# Sheet2.net
KiCad netlist of a schematic drawn in Altium Designer
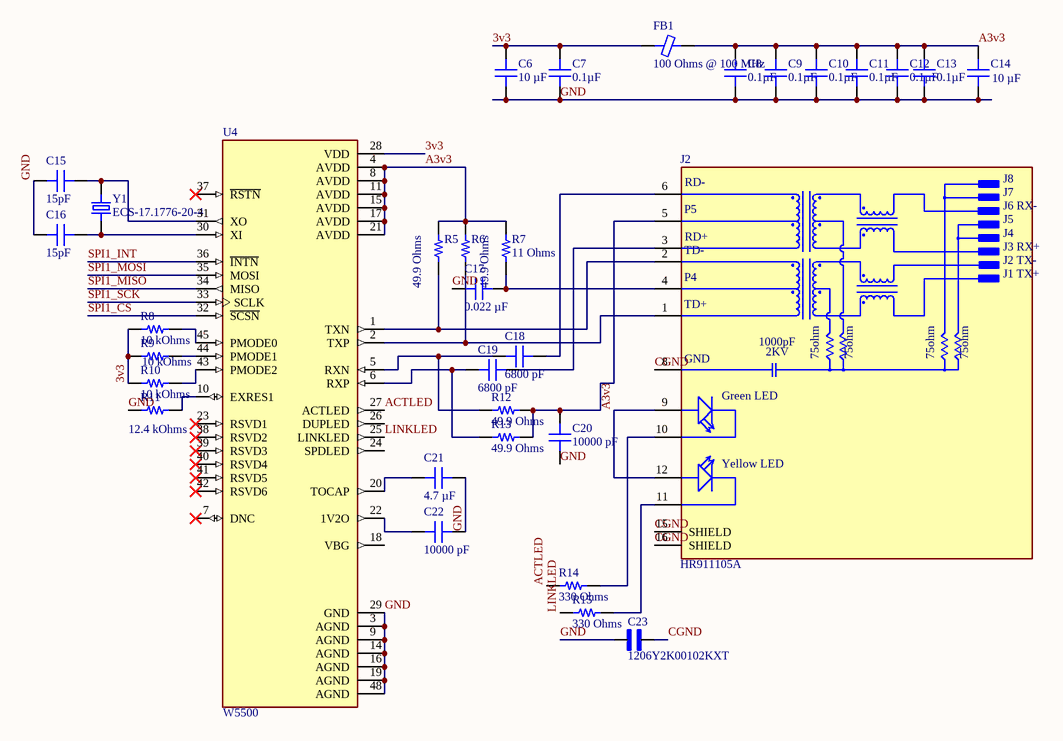
[diagram p0: Sheet2.SchDoc]

(export (version "E")
  (design (tool "Eeschema 10.0.6"))
  (components
    (comp (ref "C6")
      (value "10 µF")
      (footprint "CAP 1206_3216 - 0.8MM")
      (description "CAP CER 10UF 16V X5R 1206")
      (fields
        (field (name "PART NUMBER") "EMK316BJ106MD-T")
        (field (name "CAPACITANCE") "10 µF")
        (field (name "MANUFACTURER") "Taiyo Yuden")
      )
      (libsource (lib "Celestial Altium Library - altium_library") (part "Capacitor"))
    )
    (comp (ref "C7")
      (value "1µF")
      (footprint "CAP 0805_2012")
      (description "CAP CER 1UF 10V X7R 0805")
      (fields
        (field (name "PART NUMBER") "0805ZC105KAT4A")
        (field (name "CAPACITANCE") "0.1µF")
        (field (name "MANUFACTURER") "AVX Corporation")
      )
      (libsource (lib "Celestial Altium Library - altium_library") (part "Capacitor"))
    )
    (comp (ref "C8")
      (value "1µF")
      (footprint "CAP 0805_2012")
      (description "CAP CER 1UF 10V X7R 0805")
      (fields
        (field (name "PART NUMBER") "0805ZC105KAT4A")
        (field (name "CAPACITANCE") "0.1µF")
        (field (name "MANUFACTURER") "AVX Corporation")
      )
      (libsource (lib "Celestial Altium Library - altium_library") (part "Capacitor"))
    )
    (comp (ref "C9")
      (value "1µF")
      (footprint "CAP 0805_2012")
      (description "CAP CER 1UF 10V X7R 0805")
      (fields
        (field (name "PART NUMBER") "0805ZC105KAT4A")
        (field (name "CAPACITANCE") "0.1µF")
        (field (name "MANUFACTURER") "AVX Corporation")
      )
      (libsource (lib "Celestial Altium Library - altium_library") (part "Capacitor"))
    )
    (comp (ref "C10")
      (value "1µF")
      (footprint "CAP 0805_2012")
      (description "CAP CER 1UF 10V X7R 0805")
      (fields
        (field (name "PART NUMBER") "0805ZC105KAT4A")
        (field (name "CAPACITANCE") "0.1µF")
        (field (name "MANUFACTURER") "AVX Corporation")
      )
      (libsource (lib "Celestial Altium Library - altium_library") (part "Capacitor"))
    )
    (comp (ref "C11")
      (value "1µF")
      (footprint "CAP 0805_2012")
      (description "CAP CER 1UF 10V X7R 0805")
      (fields
        (field (name "PART NUMBER") "0805ZC105KAT4A")
        (field (name "CAPACITANCE") "0.1µF")
        (field (name "MANUFACTURER") "AVX Corporation")
      )
      (libsource (lib "Celestial Altium Library - altium_library") (part "Capacitor"))
    )
    (comp (ref "C12")
      (value "1µF")
      (footprint "CAP 0805_2012")
      (description "CAP CER 1UF 10V X7R 0805")
      (fields
        (field (name "PART NUMBER") "0805ZC105KAT4A")
        (field (name "CAPACITANCE") "0.1µF")
        (field (name "MANUFACTURER") "AVX Corporation")
      )
      (libsource (lib "Celestial Altium Library - altium_library") (part "Capacitor"))
    )
    (comp (ref "C13")
      (value "1µF")
      (footprint "CAP 0805_2012")
      (description "CAP CER 1UF 10V X7R 0805")
      (fields
        (field (name "PART NUMBER") "0805ZC105KAT4A")
        (field (name "CAPACITANCE") "0.1µF")
        (field (name "MANUFACTURER") "AVX Corporation")
      )
      (libsource (lib "Celestial Altium Library - altium_library") (part "Capacitor"))
    )
    (comp (ref "C14")
      (value "10 µF")
      (footprint "CAP 1206_3216 - 0.8MM")
      (description "CAP CER 10UF 16V X5R 1206")
      (fields
        (field (name "PART NUMBER") "EMK316BJ106MD-T")
        (field (name "CAPACITANCE") "10 µF")
        (field (name "MANUFACTURER") "Taiyo Yuden")
      )
      (libsource (lib "Celestial Altium Library - altium_library") (part "Capacitor"))
    )
    (comp (ref "C15")
      (value "15pF")
      (footprint "CAP 0805_2012")
      (description "CAP CER 15PF 50V C0G/NP0 0805")
      (fields
        (field (name "PART NUMBER") "08055A150JAT2A")
        (field (name "CAPACITANCE") "15pF")
        (field (name "MANUFACTURER") "AVX Corporation")
      )
      (libsource (lib "Celestial Altium Library - altium_library") (part "Capacitor"))
    )
    (comp (ref "C16")
      (value "15pF")
      (footprint "CAP 0805_2012")
      (description "CAP CER 15PF 50V C0G/NP0 0805")
      (fields
        (field (name "PART NUMBER") "08055A150JAT2A")
        (field (name "CAPACITANCE") "15pF")
        (field (name "MANUFACTURER") "AVX Corporation")
      )
      (libsource (lib "Celestial Altium Library - altium_library") (part "Capacitor"))
    )
    (comp (ref "C17")
      (value "0.022 µF")
      (footprint "CAP 0805_2012")
      (description "CAP CER 0805 22NF 50V X7R 10%")
      (fields
        (field (name "PART NUMBER") "C0805C223K5RECAUTO")
        (field (name "CAPACITANCE") "0.022 µF")
        (field (name "MANUFACTURER") "KEMET")
      )
      (libsource (lib "Celestial Altium Library - altium_library") (part "Capacitor"))
    )
    (comp (ref "C18")
      (value "6800 pF")
      (footprint "CAP 0805_2012")
      (description "CAP CER 0805 6.8NF 25V C0G 20%")
      (fields
        (field (name "PART NUMBER") "C0805C682M3GEC7800")
        (field (name "CAPACITANCE") "6800 pF")
        (field (name "MANUFACTURER") "KEMET")
      )
      (libsource (lib "Celestial Altium Library - altium_library") (part "Capacitor"))
    )
    (comp (ref "C19")
      (value "6800 pF")
      (footprint "CAP 0805_2012")
      (description "CAP CER 0805 6.8NF 25V C0G 20%")
      (fields
        (field (name "PART NUMBER") "C0805C682M3GEC7800")
        (field (name "CAPACITANCE") "6800 pF")
        (field (name "MANUFACTURER") "KEMET")
      )
      (libsource (lib "Celestial Altium Library - altium_library") (part "Capacitor"))
    )
    (comp (ref "C20")
      (value "10000 pF")
      (footprint "CAP 0805_2012")
      (description "CAP CER 0805 10NF 100V X7R")
      (fields
        (field (name "PART NUMBER") "C0805X103K1RAC3316")
        (field (name "CAPACITANCE") "10000 pF")
        (field (name "MANUFACTURER") "KEMET")
      )
      (libsource (lib "Celestial Altium Library - altium_library") (part "Capacitor"))
    )
    (comp (ref "C21")
      (value "4.7 µF")
      (footprint "CAP 0805_2012")
      (description "4.70UF 25.0V")
      (fields
        (field (name "PART NUMBER") "C0805X475M3RAC7800")
        (field (name "CAPACITANCE") "4.7 µF")
        (field (name "MANUFACTURER") "KEMET")
      )
      (libsource (lib "Celestial Altium Library - altium_library") (part "Capacitor"))
    )
    (comp (ref "C22")
      (value "10000 pF")
      (footprint "CAP 0805_2012")
      (description "CAP CER 0805 10NF 100V X7R")
      (fields
        (field (name "PART NUMBER") "C0805X103K1RAC3316")
        (field (name "CAPACITANCE") "10000 pF")
        (field (name "MANUFACTURER") "KEMET")
      )
      (libsource (lib "Celestial Altium Library - altium_library") (part "Capacitor"))
    )
    (comp (ref "C23")
      (value "1206Y2K00102KXT")
      (footprint "CAPC3216X160N")
      (description "1000 pF Â±10% 2000V (2kV) Ceramic Capacitor X7R 1206 (3216 Metric)")
      (fields (field (name "MF") "Knowles Syfer"))
      (libsource (lib "1206Y2K00102KXT") (part "1206Y2K00102KXT"))
    )
    (comp (ref "FB1")
      (value "100 Ohms @ 100 MHz")
      (footprint "FER 0805_2012")
      (description "FERRITE BEAD, CHIP, 0805, 100 OH")
      (fields (field (name "PART NUMBER") "HRB0805S101K1.00FT") (field (name "MANUFACTURER") "AEM, Inc."))
      (libsource (lib "Celestial Altium Library - altium_library") (part "Ferrite Chip"))
    )
    (comp (ref "J2")
      (value "HR911105A")
      (footprint "HANRUN_HR911105A")
      (description "DIP RJ45 Connector;")
      (fields (field (name "MF") "hanrun"))
      (libsource (lib "HR911105A") (part "HR911105A"))
    )
    (comp (ref "R5")
      (value "49.9 Ohms")
      (footprint "RES 0805_2012")
      (description "RCC0805 100 49R9 1% ET1 E3")
      (fields (field (name "PART NUMBER") "RCC080549R9FKEA") (field (name "MANUFACTURER") "Vishay Dale"))
      (libsource (lib "Celestial Altium Library - altium_library") (part "Resistor"))
    )
    (comp (ref "R6")
      (value "49.9 Ohms")
      (footprint "RES 0805_2012")
      (description "RCC0805 100 49R9 1% ET1 E3")
      (fields (field (name "PART NUMBER") "RCC080549R9FKEA") (field (name "MANUFACTURER") "Vishay Dale"))
      (libsource (lib "Celestial Altium Library - altium_library") (part "Resistor"))
    )
    (comp (ref "R7")
      (value "11 Ohms")
      (footprint "RES 0805_2012")
      (description "RES SMD 11 OHM 1% 1/8W 0805")
      (fields (field (name "PART NUMBER") "KTR10EZPF11R0") (field (name "MANUFACTURER") "Rohm Semiconductor"))
      (libsource (lib "Celestial Altium Library - altium_library") (part "Resistor"))
    )
    (comp (ref "R8")
      (value "10 kOhms")
      (footprint "RES 0805_2012")
      (description "RES 10K OHM 0.1% 1/10W 0805")
      (fields
        (field (name "PART NUMBER") "RNCS0805BKE10K0")
        (field (name "MANUFACTURER") "Stackpole Electronics Inc")
      )
      (libsource (lib "Celestial Altium Library - altium_library") (part "Resistor"))
    )
    (comp (ref "R9")
      (value "10 kOhms")
      (footprint "RES 0805_2012")
      (description "RES 10K OHM 0.1% 1/10W 0805")
      (fields
        (field (name "PART NUMBER") "RNCS0805BKE10K0")
        (field (name "MANUFACTURER") "Stackpole Electronics Inc")
      )
      (libsource (lib "Celestial Altium Library - altium_library") (part "Resistor"))
    )
    (comp (ref "R10")
      (value "10 kOhms")
      (footprint "RES 0805_2012")
      (description "RES 10K OHM 0.1% 1/10W 0805")
      (fields
        (field (name "PART NUMBER") "RNCS0805BKE10K0")
        (field (name "MANUFACTURER") "Stackpole Electronics Inc")
      )
      (libsource (lib "Celestial Altium Library - altium_library") (part "Resistor"))
    )
    (comp (ref "R11")
      (value "12.4 kOhms")
      (footprint "RES 0805_2012")
      (description "RES 12.4 KOHMS 0.1% 1/5W 0805")
      (fields
        (field (name "PART NUMBER") "RQ73C2A12K4BTD")
        (field (name "MANUFACTURER") "TE Connectivity Passive Product")
      )
      (libsource (lib "Celestial Altium Library - altium_library") (part "Resistor"))
    )
    (comp (ref "R12")
      (value "49.9 Ohms")
      (footprint "RES 0805_2012")
      (description "RCC0805 100 49R9 1% ET1 E3")
      (fields (field (name "PART NUMBER") "RCC080549R9FKEA") (field (name "MANUFACTURER") "Vishay Dale"))
      (libsource (lib "Celestial Altium Library - altium_library") (part "Resistor"))
    )
    (comp (ref "R13")
      (value "49.9 Ohms")
      (footprint "RES 0805_2012")
      (description "RCC0805 100 49R9 1% ET1 E3")
      (fields (field (name "PART NUMBER") "RCC080549R9FKEA") (field (name "MANUFACTURER") "Vishay Dale"))
      (libsource (lib "Celestial Altium Library - altium_library") (part "Resistor"))
    )
    (comp (ref "R14")
      (value "330 Ohms")
      (footprint "YAGEO RES 0805_2012")
      (description "RES 330 OHM 1% 1/8W 0805")
      (fields (field (name "PART NUMBER") "RC0805FR-07330RL") (field (name "MANUFACTURER") "Yageo"))
      (libsource (lib "Celestial Altium Library - altium_library") (part "Resistor"))
    )
    (comp (ref "R15")
      (value "330 Ohms")
      (footprint "YAGEO RES 0805_2012")
      (description "RES 330 OHM 1% 1/8W 0805")
      (fields (field (name "PART NUMBER") "RC0805FR-07330RL") (field (name "MANUFACTURER") "Yageo"))
      (libsource (lib "Celestial Altium Library - altium_library") (part "Resistor"))
    )
    (comp (ref "U4")
      (value "W5500")
      (footprint "QFP50P900X900X160-48N")
      (description "Hardwired TCP/IP embedded Ethernet controller")
      (libsource (lib "W5500") (part "W5500"))
    )
    (comp (ref "Y1")
      (value "ECS-17.1776-20-4")
      (footprint "XTAL_ECS-160-20-4X")
      (description "Crystals 17.1776MHz HC49S")
      (fields (field (name "MF") "ECS International"))
      (libsource (lib "ECS-17.1776-20-4") (part "ECS-17.1776-20-4"))
    )
  )
  (nets
    (net (code "1") (name "/3v3") (class "Default")
      (node (ref "C6") (pin "2") (pinfunction "2_2") (pintype "passive"))
      (node (ref "C7") (pin "2") (pinfunction "2_2") (pintype "passive"))
      (node (ref "FB1") (pin "1") (pinfunction "1_1") (pintype "passive"))
      (node (ref "R10") (pin "1") (pinfunction "1_1") (pintype "passive"))
      (node (ref "R8") (pin "1") (pinfunction "1_1") (pintype "passive"))
      (node (ref "R9") (pin "1") (pinfunction "1_1") (pintype "passive"))
      (node (ref "U4") (pin "28") (pinfunction "VDD_28") (pintype "power_in"))
    )
    (net (code "2") (name "/A3v3") (class "Default")
      (node (ref "C10") (pin "2") (pinfunction "2_2") (pintype "passive"))
      (node (ref "C11") (pin "2") (pinfunction "2_2") (pintype "passive"))
      (node (ref "C12") (pin "2") (pinfunction "2_2") (pintype "passive"))
      (node (ref "C13") (pin "2") (pinfunction "2_2") (pintype "passive"))
      (node (ref "C14") (pin "2") (pinfunction "2_2") (pintype "passive"))
      (node (ref "C8") (pin "2") (pinfunction "2_2") (pintype "passive"))
      (node (ref "C9") (pin "2") (pinfunction "2_2") (pintype "passive"))
      (node (ref "FB1") (pin "2") (pinfunction "2_2") (pintype "passive"))
      (node (ref "J2") (pin "12") (pinfunction "YA_12") (pintype "passive"))
      (node (ref "J2") (pin "9") (pinfunction "GA_9") (pintype "passive"))
      (node (ref "R5") (pin "2") (pinfunction "2_2") (pintype "passive"))
      (node (ref "R6") (pin "2") (pinfunction "2_2") (pintype "passive"))
      (node (ref "R7") (pin "2") (pinfunction "2_2") (pintype "passive"))
      (node (ref "U4") (pin "11") (pinfunction "AVDD_11") (pintype "power_in"))
      (node (ref "U4") (pin "15") (pinfunction "AVDD_15") (pintype "power_in"))
      (node (ref "U4") (pin "17") (pinfunction "AVDD_17") (pintype "power_in"))
      (node (ref "U4") (pin "21") (pinfunction "AVDD_21") (pintype "power_in"))
      (node (ref "U4") (pin "4") (pinfunction "AVDD_4") (pintype "power_in"))
      (node (ref "U4") (pin "8") (pinfunction "AVDD_8") (pintype "power_in"))
    )
    (net (code "3") (name "/ACTLED") (class "Default")
      (node (ref "R14") (pin "1") (pinfunction "1_1") (pintype "passive"))
      (node (ref "U4") (pin "27") (pinfunction "ACTLED_27") (pintype "output"))
    )
    (net (code "4") (name "/CGND") (class "Default")
      (node (ref "C23") (pin "2") (pinfunction "2_2") (pintype "passive"))
      (node (ref "J2") (pin "15") (pinfunction "SHIELD_15") (pintype "passive"))
      (node (ref "J2") (pin "16") (pinfunction "SHIELD_16") (pintype "passive"))
      (node (ref "J2") (pin "8") (pinfunction "GND_8") (pintype "power_in"))
    )
    (net (code "5") (name "/GND") (class "Default")
      (node (ref "C10") (pin "1") (pinfunction "1_1") (pintype "passive"))
      (node (ref "C11") (pin "1") (pinfunction "1_1") (pintype "passive"))
      (node (ref "C12") (pin "1") (pinfunction "1_1") (pintype "passive"))
      (node (ref "C13") (pin "1") (pinfunction "1_1") (pintype "passive"))
      (node (ref "C14") (pin "1") (pinfunction "1_1") (pintype "passive"))
      (node (ref "C15") (pin "1") (pinfunction "1_1") (pintype "passive"))
      (node (ref "C16") (pin "1") (pinfunction "1_1") (pintype "passive"))
      (node (ref "C17") (pin "2") (pinfunction "2_2") (pintype "passive"))
      (node (ref "C20") (pin "1") (pinfunction "1_1") (pintype "passive"))
      (node (ref "C21") (pin "2") (pinfunction "2_2") (pintype "passive"))
      (node (ref "C22") (pin "2") (pinfunction "2_2") (pintype "passive"))
      (node (ref "C23") (pin "1") (pinfunction "1_1") (pintype "passive"))
      (node (ref "C6") (pin "1") (pinfunction "1_1") (pintype "passive"))
      (node (ref "C7") (pin "1") (pinfunction "1_1") (pintype "passive"))
      (node (ref "C8") (pin "1") (pinfunction "1_1") (pintype "passive"))
      (node (ref "C9") (pin "1") (pinfunction "1_1") (pintype "passive"))
      (node (ref "R11") (pin "1") (pinfunction "1_1") (pintype "passive"))
      (node (ref "U4") (pin "14") (pinfunction "AGND_14") (pintype "power_in"))
      (node (ref "U4") (pin "16") (pinfunction "AGND_16") (pintype "power_in"))
      (node (ref "U4") (pin "19") (pinfunction "AGND_19") (pintype "power_in"))
      (node (ref "U4") (pin "29") (pinfunction "GND_29") (pintype "passive"))
      (node (ref "U4") (pin "3") (pinfunction "AGND_3") (pintype "power_in"))
      (node (ref "U4") (pin "48") (pinfunction "AGND_48") (pintype "power_in"))
      (node (ref "U4") (pin "9") (pinfunction "AGND_9") (pintype "power_in"))
    )
    (net (code "6") (name "/LINKLED") (class "Default")
      (node (ref "R15") (pin "1") (pinfunction "1_1") (pintype "passive"))
      (node (ref "U4") (pin "25") (pinfunction "LINKLED_25") (pintype "output"))
    )
    (net (code "7") (name "/SPI1_CS") (class "Default")
      (node (ref "U4") (pin "32") (pinfunction "~{SCSN}_32") (pintype "input"))
    )
    (net (code "8") (name "/SPI1_INT") (class "Default")
      (node (ref "U4") (pin "36") (pinfunction "~{INTN}_36") (pintype "input"))
    )
    (net (code "9") (name "/SPI1_MISO") (class "Default")
      (node (ref "U4") (pin "34") (pinfunction "MISO_34") (pintype "output"))
    )
    (net (code "10") (name "/SPI1_MOSI") (class "Default")
      (node (ref "U4") (pin "35") (pinfunction "MOSI_35") (pintype "input"))
    )
    (net (code "11") (name "/SPI1_SCK") (class "Default")
      (node (ref "U4") (pin "33") (pinfunction "SCLK_33") (pintype "input"))
    )
    (net (code "12") (name "Net-(J2-GC)") (class "Default")
      (node (ref "J2") (pin "10") (pinfunction "GC_10") (pintype "passive"))
      (node (ref "R14") (pin "2") (pinfunction "2_2") (pintype "passive"))
    )
    (net (code "13") (name "Net-(J2-P4)") (class "Default")
      (node (ref "C17") (pin "1") (pinfunction "1_1") (pintype "passive"))
      (node (ref "J2") (pin "4") (pinfunction "P4_4") (pintype "passive"))
      (node (ref "R7") (pin "1") (pinfunction "1_1") (pintype "passive"))
    )
    (net (code "14") (name "Net-(J2-P5)") (class "Default")
      (node (ref "C20") (pin "2") (pinfunction "2_2") (pintype "passive"))
      (node (ref "J2") (pin "5") (pinfunction "P5_5") (pintype "passive"))
      (node (ref "R12") (pin "1") (pinfunction "1_1") (pintype "passive"))
      (node (ref "R13") (pin "1") (pinfunction "1_1") (pintype "passive"))
    )
    (net (code "15") (name "Net-(J2-RD+)") (class "Default")
      (node (ref "C19") (pin "2") (pinfunction "2_2") (pintype "passive"))
      (node (ref "J2") (pin "3") (pinfunction "RD+_3") (pintype "passive"))
    )
    (net (code "16") (name "Net-(J2-RD-)") (class "Default")
      (node (ref "C18") (pin "2") (pinfunction "2_2") (pintype "passive"))
      (node (ref "J2") (pin "6") (pinfunction "RD-_6") (pintype "passive"))
    )
    (net (code "17") (name "Net-(J2-TD+)") (class "Default")
      (node (ref "J2") (pin "1") (pinfunction "TD+_1") (pintype "passive"))
      (node (ref "R6") (pin "1") (pinfunction "1_1") (pintype "passive"))
      (node (ref "U4") (pin "2") (pinfunction "TXP_2") (pintype "output"))
    )
    (net (code "18") (name "Net-(J2-TD-)") (class "Default")
      (node (ref "J2") (pin "2") (pinfunction "TD-_2") (pintype "passive"))
      (node (ref "R5") (pin "1") (pinfunction "1_1") (pintype "passive"))
      (node (ref "U4") (pin "1") (pinfunction "TXN_1") (pintype "output"))
    )
    (net (code "19") (name "Net-(J2-YC)") (class "Default")
      (node (ref "J2") (pin "11") (pinfunction "YC_11") (pintype "passive"))
      (node (ref "R15") (pin "2") (pinfunction "2_2") (pintype "passive"))
    )
    (net (code "20") (name "Net-(U4-1V2O)") (class "Default")
      (node (ref "C22") (pin "1") (pinfunction "1_1") (pintype "passive"))
      (node (ref "U4") (pin "22") (pinfunction "1V2O_22") (pintype "output"))
    )
    (net (code "21") (name "Net-(U4-EXRES1)") (class "Default")
      (node (ref "R11") (pin "2") (pinfunction "2_2") (pintype "passive"))
      (node (ref "U4") (pin "10") (pinfunction "EXRES1_10") (pintype "bidirectional"))
    )
    (net (code "22") (name "Net-(U4-PMODE0)") (class "Default")
      (node (ref "R8") (pin "2") (pinfunction "2_2") (pintype "passive"))
      (node (ref "U4") (pin "45") (pinfunction "PMODE0_45") (pintype "input"))
    )
    (net (code "23") (name "Net-(U4-PMODE1)") (class "Default")
      (node (ref "R9") (pin "2") (pinfunction "2_2") (pintype "passive"))
      (node (ref "U4") (pin "44") (pinfunction "PMODE1_44") (pintype "input"))
    )
    (net (code "24") (name "Net-(U4-PMODE2)") (class "Default")
      (node (ref "R10") (pin "2") (pinfunction "2_2") (pintype "passive"))
      (node (ref "U4") (pin "43") (pinfunction "PMODE2_43") (pintype "input"))
    )
    (net (code "25") (name "Net-(U4-RXN)") (class "Default")
      (node (ref "C18") (pin "1") (pinfunction "1_1") (pintype "passive"))
      (node (ref "R12") (pin "2") (pinfunction "2_2") (pintype "passive"))
      (node (ref "U4") (pin "5") (pinfunction "RXN_5") (pintype "input"))
    )
    (net (code "26") (name "Net-(U4-RXP)") (class "Default")
      (node (ref "C19") (pin "1") (pinfunction "1_1") (pintype "passive"))
      (node (ref "R13") (pin "2") (pinfunction "2_2") (pintype "passive"))
      (node (ref "U4") (pin "6") (pinfunction "RXP_6") (pintype "input"))
    )
    (net (code "27") (name "Net-(U4-TOCAP)") (class "Default")
      (node (ref "C21") (pin "1") (pinfunction "1_1") (pintype "passive"))
      (node (ref "U4") (pin "20") (pinfunction "TOCAP_20") (pintype "output"))
    )
    (net (code "28") (name "Net-(U4-XI)") (class "Default")
      (node (ref "C16") (pin "2") (pinfunction "2_2") (pintype "passive"))
      (node (ref "U4") (pin "30") (pinfunction "XI_30") (pintype "input"))
      (node (ref "Y1") (pin "1") (pinfunction "1_1") (pintype "passive"))
    )
    (net (code "29") (name "Net-(U4-XO)") (class "Default")
      (node (ref "C15") (pin "2") (pinfunction "2_2") (pintype "passive"))
      (node (ref "U4") (pin "31") (pinfunction "XO_31") (pintype "output"))
      (node (ref "Y1") (pin "2") (pinfunction "2_2") (pintype "passive"))
    )
    (net (code "30") (name "unconnected-(U4-DNC-Pad7)") (class "Default")
      (node (ref "U4") (pin "7") (pinfunction "DNC_7") (pintype "bidirectional+no_connect"))
    )
    (net (code "31") (name "unconnected-(U4-DUPLED-Pad26)") (class "Default")
      (node (ref "U4") (pin "26") (pinfunction "DUPLED_26") (pintype "output"))
    )
    (net (code "32") (name "unconnected-(U4-RSVD1-Pad23)") (class "Default")
      (node (ref "U4") (pin "23") (pinfunction "RSVD1_23") (pintype "input+no_connect"))
    )
    (net (code "33") (name "unconnected-(U4-RSVD2-Pad38)") (class "Default")
      (node (ref "U4") (pin "38") (pinfunction "RSVD2_38") (pintype "input+no_connect"))
    )
    (net (code "34") (name "unconnected-(U4-RSVD3-Pad39)") (class "Default")
      (node (ref "U4") (pin "39") (pinfunction "RSVD3_39") (pintype "input+no_connect"))
    )
    (net (code "35") (name "unconnected-(U4-RSVD4-Pad40)") (class "Default")
      (node (ref "U4") (pin "40") (pinfunction "RSVD4_40") (pintype "input+no_connect"))
    )
    (net (code "36") (name "unconnected-(U4-RSVD5-Pad41)") (class "Default")
      (node (ref "U4") (pin "41") (pinfunction "RSVD5_41") (pintype "input+no_connect"))
    )
    (net (code "37") (name "unconnected-(U4-RSVD6-Pad42)") (class "Default")
      (node (ref "U4") (pin "42") (pinfunction "RSVD6_42") (pintype "input+no_connect"))
    )
    (net (code "38") (name "unconnected-(U4-SPDLED-Pad24)") (class "Default")
      (node (ref "U4") (pin "24") (pinfunction "SPDLED_24") (pintype "output"))
    )
    (net (code "39") (name "unconnected-(U4-VBG-Pad18)") (class "Default")
      (node (ref "U4") (pin "18") (pinfunction "VBG_18") (pintype "output"))
    )
    (net (code "40") (name "unconnected-(U4-~{RSTN}-Pad37)") (class "Default")
      (node (ref "U4") (pin "37") (pinfunction "~{RSTN}_37") (pintype "input+no_connect"))
    )
  )
)
